# M622A.net
KiCad netlist of a schematic drawn in EAGLE
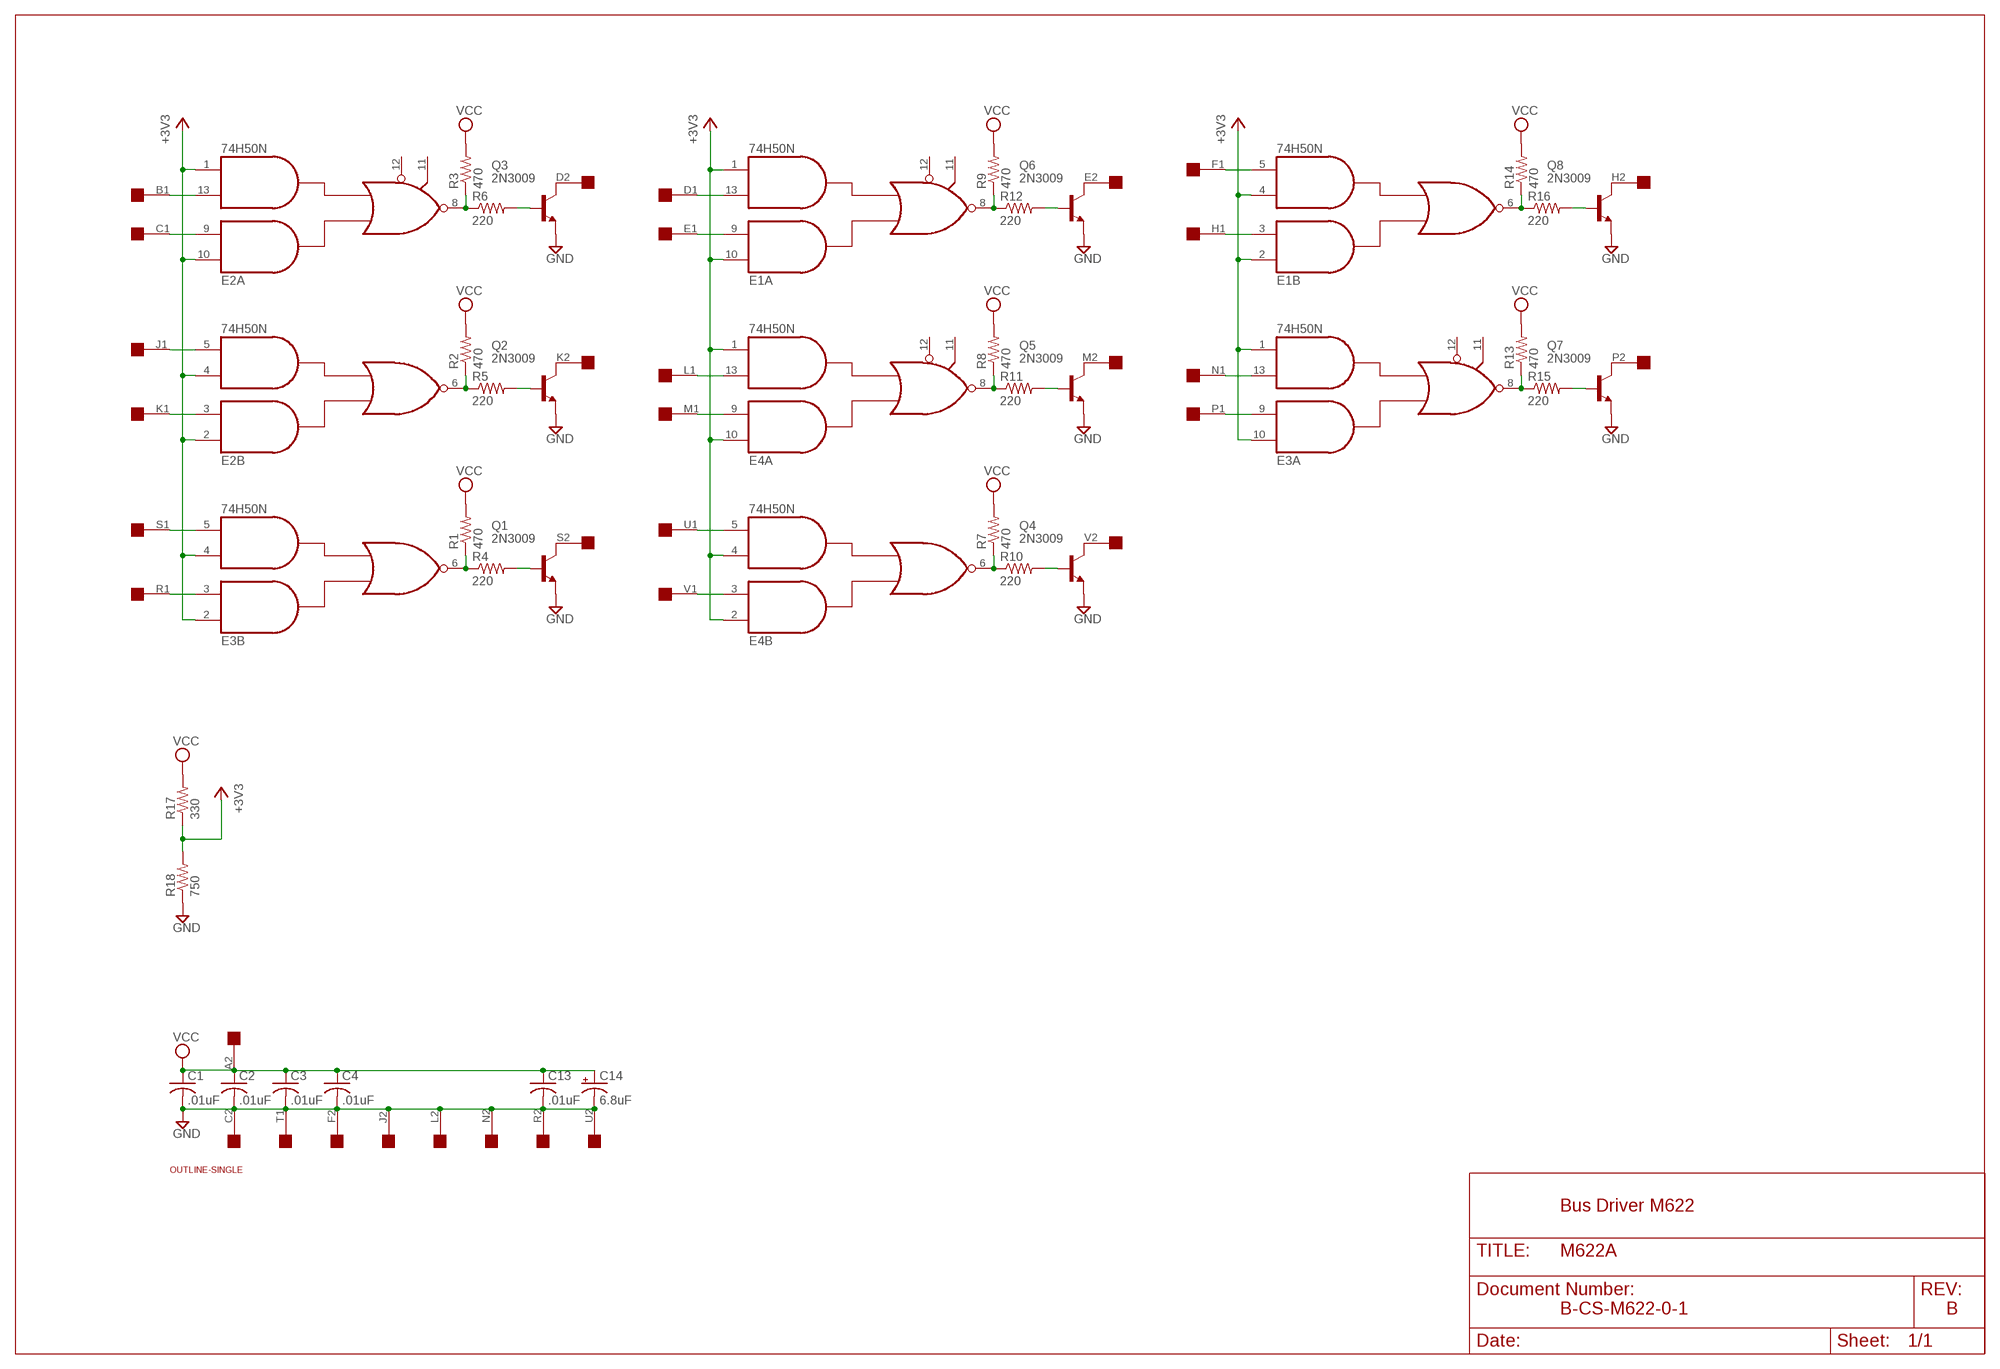
[diagram p0: schematic, sheet 1]

(export (version "E")
  (design (tool "Eeschema 10.0.6"))
  (components
    (comp (ref "C1")
      (value ".01uF")
      (footprint "eagle-import:C050-025X075")
      (libsource (lib "eagle-import") (part "C-US050-025X075"))
    )
    (comp (ref "C2")
      (value ".01uF")
      (footprint "eagle-import:C050-025X075")
      (libsource (lib "eagle-import") (part "C-US050-025X075"))
    )
    (comp (ref "C3")
      (value ".01uF")
      (footprint "eagle-import:C050-025X075")
      (libsource (lib "eagle-import") (part "C-US050-025X075"))
    )
    (comp (ref "C4")
      (value ".01uF")
      (footprint "eagle-import:C050-025X075")
      (libsource (lib "eagle-import") (part "C-US050-025X075"))
    )
    (comp (ref "C13")
      (value ".01uF")
      (footprint "eagle-import:C050-025X075")
      (libsource (lib "eagle-import") (part "C-US050-025X075"))
    )
    (comp (ref "C14")
      (value "6.8uF")
      (footprint "eagle-import:E12-8")
      (libsource (lib "eagle-import") (part "CPOL-USE20-8AXIAL"))
    )
    (comp (ref "E1")
      (value "74H50N")
      (footprint "eagle-import:DIL14")
      (libsource (lib "eagle-import") (part "7450N"))
    )
    (comp (ref "E2")
      (value "74H50N")
      (footprint "eagle-import:DIL14")
      (libsource (lib "eagle-import") (part "7450N"))
    )
    (comp (ref "E3")
      (value "74H50N")
      (footprint "eagle-import:DIL14")
      (libsource (lib "eagle-import") (part "7450N"))
    )
    (comp (ref "E4")
      (value "74H50N")
      (footprint "eagle-import:DIL14")
      (libsource (lib "eagle-import") (part "7450N"))
    )
    (comp (ref "Q1")
      (value "2N3009")
      (footprint "eagle-import:TO5")
      (libsource (lib "eagle-import") (part "2N2102"))
    )
    (comp (ref "Q2")
      (value "2N3009")
      (footprint "eagle-import:TO5")
      (libsource (lib "eagle-import") (part "2N2102"))
    )
    (comp (ref "Q3")
      (value "2N3009")
      (footprint "eagle-import:TO5")
      (libsource (lib "eagle-import") (part "2N2102"))
    )
    (comp (ref "Q4")
      (value "2N3009")
      (footprint "eagle-import:TO5")
      (libsource (lib "eagle-import") (part "2N2102"))
    )
    (comp (ref "Q5")
      (value "2N3009")
      (footprint "eagle-import:TO5")
      (libsource (lib "eagle-import") (part "2N2102"))
    )
    (comp (ref "Q6")
      (value "2N3009")
      (footprint "eagle-import:TO5")
      (libsource (lib "eagle-import") (part "2N2102"))
    )
    (comp (ref "Q7")
      (value "2N3009")
      (footprint "eagle-import:TO5")
      (libsource (lib "eagle-import") (part "2N2102"))
    )
    (comp (ref "Q8")
      (value "2N3009")
      (footprint "eagle-import:TO5")
      (libsource (lib "eagle-import") (part "2N2102"))
    )
    (comp (ref "R1")
      (value "470")
      (footprint "eagle-import:0207_10")
      (libsource (lib "eagle-import") (part "R-US_0207/10"))
    )
    (comp (ref "R2")
      (value "470")
      (footprint "eagle-import:0207_10")
      (libsource (lib "eagle-import") (part "R-US_0207/10"))
    )
    (comp (ref "R3")
      (value "470")
      (footprint "eagle-import:0207_10")
      (libsource (lib "eagle-import") (part "R-US_0207/10"))
    )
    (comp (ref "R4")
      (value "220")
      (footprint "eagle-import:0207_10")
      (libsource (lib "eagle-import") (part "R-US_0207/10"))
    )
    (comp (ref "R5")
      (value "220")
      (footprint "eagle-import:0207_10")
      (libsource (lib "eagle-import") (part "R-US_0207/10"))
    )
    (comp (ref "R6")
      (value "220")
      (footprint "eagle-import:0207_10")
      (libsource (lib "eagle-import") (part "R-US_0207/10"))
    )
    (comp (ref "R7")
      (value "470")
      (footprint "eagle-import:0207_10")
      (libsource (lib "eagle-import") (part "R-US_0207/10"))
    )
    (comp (ref "R8")
      (value "470")
      (footprint "eagle-import:0207_10")
      (libsource (lib "eagle-import") (part "R-US_0207/10"))
    )
    (comp (ref "R9")
      (value "470")
      (footprint "eagle-import:0207_10")
      (libsource (lib "eagle-import") (part "R-US_0207/10"))
    )
    (comp (ref "R10")
      (value "220")
      (footprint "eagle-import:0207_10")
      (libsource (lib "eagle-import") (part "R-US_0207/10"))
    )
    (comp (ref "R11")
      (value "220")
      (footprint "eagle-import:0207_10")
      (libsource (lib "eagle-import") (part "R-US_0207/10"))
    )
    (comp (ref "R12")
      (value "220")
      (footprint "eagle-import:0207_10")
      (libsource (lib "eagle-import") (part "R-US_0207/10"))
    )
    (comp (ref "R13")
      (value "470")
      (footprint "eagle-import:0207_10")
      (libsource (lib "eagle-import") (part "R-US_0207/10"))
    )
    (comp (ref "R14")
      (value "470")
      (footprint "eagle-import:0207_10")
      (libsource (lib "eagle-import") (part "R-US_0207/10"))
    )
    (comp (ref "R15")
      (value "220")
      (footprint "eagle-import:0207_10")
      (libsource (lib "eagle-import") (part "R-US_0207/10"))
    )
    (comp (ref "R16")
      (value "220")
      (footprint "eagle-import:0207_10")
      (libsource (lib "eagle-import") (part "R-US_0207/10"))
    )
    (comp (ref "R17")
      (value "330")
      (footprint "eagle-import:0207_10")
      (libsource (lib "eagle-import") (part "R-US_0207/10"))
    )
    (comp (ref "R18")
      (value "750")
      (footprint "eagle-import:0207_10")
      (libsource (lib "eagle-import") (part "R-US_0207/10"))
    )
    (comp (ref "U$1")
      (value "SINGLE")
      (footprint "eagle-import:EDGE-CON2")
      (libsource (lib "eagle-import") (part "SINGLE"))
    )
    (comp (ref "U$4")
      (value "OUTLINE-SINGLE")
      (footprint "eagle-import:SINGLE")
      (libsource (lib "eagle-import") (part "OUTLINE-SINGLE"))
    )
  )
  (nets
    (net (code "1") (name "+3V3") (class "Default")
      (node (ref "E1") (pin "1") (pinfunction "I4_1") (pintype "input"))
      (node (ref "E1") (pin "10") (pinfunction "I1_10") (pintype "input"))
      (node (ref "E1") (pin "2") (pinfunction "I1_2") (pintype "input"))
      (node (ref "E1") (pin "4") (pinfunction "I3_4") (pintype "input"))
      (node (ref "E2") (pin "1") (pinfunction "I4_1") (pintype "input"))
      (node (ref "E2") (pin "10") (pinfunction "I1_10") (pintype "input"))
      (node (ref "E2") (pin "2") (pinfunction "I1_2") (pintype "input"))
      (node (ref "E2") (pin "4") (pinfunction "I3_4") (pintype "input"))
      (node (ref "E3") (pin "1") (pinfunction "I4_1") (pintype "input"))
      (node (ref "E3") (pin "10") (pinfunction "I1_10") (pintype "input"))
      (node (ref "E3") (pin "2") (pinfunction "I1_2") (pintype "input"))
      (node (ref "E3") (pin "4") (pinfunction "I3_4") (pintype "input"))
      (node (ref "E4") (pin "1") (pinfunction "I4_1") (pintype "input"))
      (node (ref "E4") (pin "10") (pinfunction "I1_10") (pintype "input"))
      (node (ref "E4") (pin "2") (pinfunction "I1_2") (pintype "input"))
      (node (ref "E4") (pin "4") (pinfunction "I3_4") (pintype "input"))
      (node (ref "R17") (pin "1") (pinfunction "1_1") (pintype "passive"))
      (node (ref "R18") (pin "2") (pinfunction "2_2") (pintype "passive"))
    )
    (net (code "2") (name "GND") (class "Default")
      (node (ref "C1") (pin "2") (pinfunction "2_2") (pintype "passive"))
      (node (ref "C13") (pin "2") (pinfunction "2_2") (pintype "passive"))
      (node (ref "C14") (pin "-") (pinfunction "-_-") (pintype "passive"))
      (node (ref "C2") (pin "2") (pinfunction "2_2") (pintype "passive"))
      (node (ref "C3") (pin "2") (pinfunction "2_2") (pintype "passive"))
      (node (ref "C4") (pin "2") (pinfunction "2_2") (pintype "passive"))
      (node (ref "Q1") (pin "1") (pinfunction "E_1") (pintype "passive"))
      (node (ref "Q2") (pin "1") (pinfunction "E_1") (pintype "passive"))
      (node (ref "Q3") (pin "1") (pinfunction "E_1") (pintype "passive"))
      (node (ref "Q4") (pin "1") (pinfunction "E_1") (pintype "passive"))
      (node (ref "Q5") (pin "1") (pinfunction "E_1") (pintype "passive"))
      (node (ref "Q6") (pin "1") (pinfunction "E_1") (pintype "passive"))
      (node (ref "Q7") (pin "1") (pinfunction "E_1") (pintype "passive"))
      (node (ref "Q8") (pin "1") (pinfunction "E_1") (pintype "passive"))
      (node (ref "R18") (pin "1") (pinfunction "1_1") (pintype "passive"))
      (node (ref "U$1") (pin "C2") (pinfunction "1_C2") (pintype "bidirectional"))
      (node (ref "U$1") (pin "F2") (pinfunction "1_F2") (pintype "bidirectional"))
      (node (ref "U$1") (pin "J2") (pinfunction "1_J2") (pintype "bidirectional"))
      (node (ref "U$1") (pin "L2") (pinfunction "1_L2") (pintype "bidirectional"))
      (node (ref "U$1") (pin "N2") (pinfunction "1_N2") (pintype "bidirectional"))
      (node (ref "U$1") (pin "R2") (pinfunction "1_R2") (pintype "bidirectional"))
      (node (ref "U$1") (pin "T1") (pinfunction "1_T1") (pintype "bidirectional"))
      (node (ref "U$1") (pin "U2") (pinfunction "1_U2") (pintype "bidirectional"))
    )
    (net (code "3") (name "Net-(E1A-I2)") (class "Default")
      (node (ref "E1") (pin "9") (pinfunction "I2_9") (pintype "input"))
      (node (ref "U$1") (pin "E1") (pinfunction "1_E1") (pintype "bidirectional"))
    )
    (net (code "4") (name "Net-(E1A-I3)") (class "Default")
      (node (ref "E1") (pin "13") (pinfunction "I3_13") (pintype "input"))
      (node (ref "U$1") (pin "D1") (pinfunction "1_D1") (pintype "bidirectional"))
    )
    (net (code "5") (name "Net-(E1A-O)") (class "Default")
      (node (ref "E1") (pin "8") (pinfunction "O_8") (pintype "output"))
      (node (ref "R12") (pin "1") (pinfunction "1_1") (pintype "passive"))
      (node (ref "R9") (pin "1") (pinfunction "1_1") (pintype "passive"))
    )
    (net (code "6") (name "Net-(E1B-I2)") (class "Default")
      (node (ref "E1") (pin "3") (pinfunction "I2_3") (pintype "input"))
      (node (ref "U$1") (pin "H1") (pinfunction "1_H1") (pintype "bidirectional"))
    )
    (net (code "7") (name "Net-(E1B-I4)") (class "Default")
      (node (ref "E1") (pin "5") (pinfunction "I4_5") (pintype "input"))
      (node (ref "U$1") (pin "F1") (pinfunction "1_F1") (pintype "bidirectional"))
    )
    (net (code "8") (name "Net-(E1B-O)") (class "Default")
      (node (ref "E1") (pin "6") (pinfunction "O_6") (pintype "output"))
      (node (ref "R14") (pin "1") (pinfunction "1_1") (pintype "passive"))
      (node (ref "R16") (pin "1") (pinfunction "1_1") (pintype "passive"))
    )
    (net (code "9") (name "Net-(E2A-I2)") (class "Default")
      (node (ref "E2") (pin "9") (pinfunction "I2_9") (pintype "input"))
      (node (ref "U$1") (pin "C1") (pinfunction "1_C1") (pintype "bidirectional"))
    )
    (net (code "10") (name "Net-(E2A-I3)") (class "Default")
      (node (ref "E2") (pin "13") (pinfunction "I3_13") (pintype "input"))
      (node (ref "U$1") (pin "B1") (pinfunction "1_B1") (pintype "bidirectional"))
    )
    (net (code "11") (name "Net-(E2A-O)") (class "Default")
      (node (ref "E2") (pin "8") (pinfunction "O_8") (pintype "output"))
      (node (ref "R3") (pin "1") (pinfunction "1_1") (pintype "passive"))
      (node (ref "R6") (pin "1") (pinfunction "1_1") (pintype "passive"))
    )
    (net (code "12") (name "Net-(E2B-I2)") (class "Default")
      (node (ref "E2") (pin "3") (pinfunction "I2_3") (pintype "input"))
      (node (ref "U$1") (pin "K1") (pinfunction "1_K1") (pintype "bidirectional"))
    )
    (net (code "13") (name "Net-(E2B-I4)") (class "Default")
      (node (ref "E2") (pin "5") (pinfunction "I4_5") (pintype "input"))
      (node (ref "U$1") (pin "J1") (pinfunction "1_J1") (pintype "bidirectional"))
    )
    (net (code "14") (name "Net-(E2B-O)") (class "Default")
      (node (ref "E2") (pin "6") (pinfunction "O_6") (pintype "output"))
      (node (ref "R2") (pin "1") (pinfunction "1_1") (pintype "passive"))
      (node (ref "R5") (pin "1") (pinfunction "1_1") (pintype "passive"))
    )
    (net (code "15") (name "Net-(E3A-I2)") (class "Default")
      (node (ref "E3") (pin "9") (pinfunction "I2_9") (pintype "input"))
      (node (ref "U$1") (pin "P1") (pinfunction "1_P1") (pintype "bidirectional"))
    )
    (net (code "16") (name "Net-(E3A-I3)") (class "Default")
      (node (ref "E3") (pin "13") (pinfunction "I3_13") (pintype "input"))
      (node (ref "U$1") (pin "N1") (pinfunction "1_N1") (pintype "bidirectional"))
    )
    (net (code "17") (name "Net-(E3A-O)") (class "Default")
      (node (ref "E3") (pin "8") (pinfunction "O_8") (pintype "output"))
      (node (ref "R13") (pin "1") (pinfunction "1_1") (pintype "passive"))
      (node (ref "R15") (pin "1") (pinfunction "1_1") (pintype "passive"))
    )
    (net (code "18") (name "Net-(E3B-I2)") (class "Default")
      (node (ref "E3") (pin "3") (pinfunction "I2_3") (pintype "input"))
      (node (ref "U$1") (pin "R1") (pinfunction "1_R1") (pintype "bidirectional"))
    )
    (net (code "19") (name "Net-(E3B-I4)") (class "Default")
      (node (ref "E3") (pin "5") (pinfunction "I4_5") (pintype "input"))
      (node (ref "U$1") (pin "S1") (pinfunction "1_S1") (pintype "bidirectional"))
    )
    (net (code "20") (name "Net-(E3B-O)") (class "Default")
      (node (ref "E3") (pin "6") (pinfunction "O_6") (pintype "output"))
      (node (ref "R1") (pin "1") (pinfunction "1_1") (pintype "passive"))
      (node (ref "R4") (pin "1") (pinfunction "1_1") (pintype "passive"))
    )
    (net (code "21") (name "Net-(E4A-I2)") (class "Default")
      (node (ref "E4") (pin "9") (pinfunction "I2_9") (pintype "input"))
      (node (ref "U$1") (pin "M1") (pinfunction "1_M1") (pintype "bidirectional"))
    )
    (net (code "22") (name "Net-(E4A-I3)") (class "Default")
      (node (ref "E4") (pin "13") (pinfunction "I3_13") (pintype "input"))
      (node (ref "U$1") (pin "L1") (pinfunction "1_L1") (pintype "bidirectional"))
    )
    (net (code "23") (name "Net-(E4A-O)") (class "Default")
      (node (ref "E4") (pin "8") (pinfunction "O_8") (pintype "output"))
      (node (ref "R11") (pin "1") (pinfunction "1_1") (pintype "passive"))
      (node (ref "R8") (pin "1") (pinfunction "1_1") (pintype "passive"))
    )
    (net (code "24") (name "Net-(E4B-I2)") (class "Default")
      (node (ref "E4") (pin "3") (pinfunction "I2_3") (pintype "input"))
      (node (ref "U$1") (pin "V1") (pinfunction "1_V1") (pintype "bidirectional"))
    )
    (net (code "25") (name "Net-(E4B-I4)") (class "Default")
      (node (ref "E4") (pin "5") (pinfunction "I4_5") (pintype "input"))
      (node (ref "U$1") (pin "U1") (pinfunction "1_U1") (pintype "bidirectional"))
    )
    (net (code "26") (name "Net-(E4B-O)") (class "Default")
      (node (ref "E4") (pin "6") (pinfunction "O_6") (pintype "output"))
      (node (ref "R10") (pin "1") (pinfunction "1_1") (pintype "passive"))
      (node (ref "R7") (pin "1") (pinfunction "1_1") (pintype "passive"))
    )
    (net (code "27") (name "Net-(Q1-B)") (class "Default")
      (node (ref "Q1") (pin "2") (pinfunction "B_2") (pintype "passive"))
      (node (ref "R4") (pin "2") (pinfunction "2_2") (pintype "passive"))
    )
    (net (code "28") (name "Net-(Q1-C)") (class "Default")
      (node (ref "Q1") (pin "3") (pinfunction "C_3") (pintype "passive"))
      (node (ref "U$1") (pin "S2") (pinfunction "1_S2") (pintype "bidirectional"))
    )
    (net (code "29") (name "Net-(Q2-B)") (class "Default")
      (node (ref "Q2") (pin "2") (pinfunction "B_2") (pintype "passive"))
      (node (ref "R5") (pin "2") (pinfunction "2_2") (pintype "passive"))
    )
    (net (code "30") (name "Net-(Q2-C)") (class "Default")
      (node (ref "Q2") (pin "3") (pinfunction "C_3") (pintype "passive"))
      (node (ref "U$1") (pin "K2") (pinfunction "1_K2") (pintype "bidirectional"))
    )
    (net (code "31") (name "Net-(Q3-B)") (class "Default")
      (node (ref "Q3") (pin "2") (pinfunction "B_2") (pintype "passive"))
      (node (ref "R6") (pin "2") (pinfunction "2_2") (pintype "passive"))
    )
    (net (code "32") (name "Net-(Q3-C)") (class "Default")
      (node (ref "Q3") (pin "3") (pinfunction "C_3") (pintype "passive"))
      (node (ref "U$1") (pin "D2") (pinfunction "1_D2") (pintype "bidirectional"))
    )
    (net (code "33") (name "Net-(Q4-B)") (class "Default")
      (node (ref "Q4") (pin "2") (pinfunction "B_2") (pintype "passive"))
      (node (ref "R10") (pin "2") (pinfunction "2_2") (pintype "passive"))
    )
    (net (code "34") (name "Net-(Q4-C)") (class "Default")
      (node (ref "Q4") (pin "3") (pinfunction "C_3") (pintype "passive"))
      (node (ref "U$1") (pin "V2") (pinfunction "1_V2") (pintype "bidirectional"))
    )
    (net (code "35") (name "Net-(Q5-B)") (class "Default")
      (node (ref "Q5") (pin "2") (pinfunction "B_2") (pintype "passive"))
      (node (ref "R11") (pin "2") (pinfunction "2_2") (pintype "passive"))
    )
    (net (code "36") (name "Net-(Q5-C)") (class "Default")
      (node (ref "Q5") (pin "3") (pinfunction "C_3") (pintype "passive"))
      (node (ref "U$1") (pin "M2") (pinfunction "1_M2") (pintype "bidirectional"))
    )
    (net (code "37") (name "Net-(Q6-B)") (class "Default")
      (node (ref "Q6") (pin "2") (pinfunction "B_2") (pintype "passive"))
      (node (ref "R12") (pin "2") (pinfunction "2_2") (pintype "passive"))
    )
    (net (code "38") (name "Net-(Q6-C)") (class "Default")
      (node (ref "Q6") (pin "3") (pinfunction "C_3") (pintype "passive"))
      (node (ref "U$1") (pin "E2") (pinfunction "1_E2") (pintype "bidirectional"))
    )
    (net (code "39") (name "Net-(Q7-B)") (class "Default")
      (node (ref "Q7") (pin "2") (pinfunction "B_2") (pintype "passive"))
      (node (ref "R15") (pin "2") (pinfunction "2_2") (pintype "passive"))
    )
    (net (code "40") (name "Net-(Q7-C)") (class "Default")
      (node (ref "Q7") (pin "3") (pinfunction "C_3") (pintype "passive"))
      (node (ref "U$1") (pin "P2") (pinfunction "1_P2") (pintype "bidirectional"))
    )
    (net (code "41") (name "Net-(Q8-B)") (class "Default")
      (node (ref "Q8") (pin "2") (pinfunction "B_2") (pintype "passive"))
      (node (ref "R16") (pin "2") (pinfunction "2_2") (pintype "passive"))
    )
    (net (code "42") (name "Net-(Q8-C)") (class "Default")
      (node (ref "Q8") (pin "3") (pinfunction "C_3") (pintype "passive"))
      (node (ref "U$1") (pin "H2") (pinfunction "1_H2") (pintype "bidirectional"))
    )
    (net (code "43") (name "VCC") (class "Default")
      (node (ref "C1") (pin "1") (pinfunction "1_1") (pintype "passive"))
      (node (ref "C13") (pin "1") (pinfunction "1_1") (pintype "passive"))
      (node (ref "C14") (pin "+") (pinfunction "+_+") (pintype "passive"))
      (node (ref "C2") (pin "1") (pinfunction "1_1") (pintype "passive"))
      (node (ref "C3") (pin "1") (pinfunction "1_1") (pintype "passive"))
      (node (ref "C4") (pin "1") (pinfunction "1_1") (pintype "passive"))
      (node (ref "R1") (pin "2") (pinfunction "2_2") (pintype "passive"))
      (node (ref "R13") (pin "2") (pinfunction "2_2") (pintype "passive"))
      (node (ref "R14") (pin "2") (pinfunction "2_2") (pintype "passive"))
      (node (ref "R17") (pin "2") (pinfunction "2_2") (pintype "passive"))
      (node (ref "R2") (pin "2") (pinfunction "2_2") (pintype "passive"))
      (node (ref "R3") (pin "2") (pinfunction "2_2") (pintype "passive"))
      (node (ref "R7") (pin "2") (pinfunction "2_2") (pintype "passive"))
      (node (ref "R8") (pin "2") (pinfunction "2_2") (pintype "passive"))
      (node (ref "R9") (pin "2") (pinfunction "2_2") (pintype "passive"))
      (node (ref "U$1") (pin "A2") (pinfunction "1_A2") (pintype "bidirectional"))
    )
    (net (code "44") (name "unconnected-(E1A-I5-Pad12)") (class "Default")
      (node (ref "E1") (pin "12") (pinfunction "I5_12") (pintype "passive"))
    )
    (net (code "45") (name "unconnected-(E1A-I6-Pad11)") (class "Default")
      (node (ref "E1") (pin "11") (pinfunction "I6_11") (pintype "passive"))
    )
    (net (code "46") (name "unconnected-(E2A-I5-Pad12)") (class "Default")
      (node (ref "E2") (pin "12") (pinfunction "I5_12") (pintype "passive"))
    )
    (net (code "47") (name "unconnected-(E2A-I6-Pad11)") (class "Default")
      (node (ref "E2") (pin "11") (pinfunction "I6_11") (pintype "passive"))
    )
    (net (code "48") (name "unconnected-(E3A-I5-Pad12)") (class "Default")
      (node (ref "E3") (pin "12") (pinfunction "I5_12") (pintype "passive"))
    )
    (net (code "49") (name "unconnected-(E3A-I6-Pad11)") (class "Default")
      (node (ref "E3") (pin "11") (pinfunction "I6_11") (pintype "passive"))
    )
    (net (code "50") (name "unconnected-(E4A-I5-Pad12)") (class "Default")
      (node (ref "E4") (pin "12") (pinfunction "I5_12") (pintype "passive"))
    )
    (net (code "51") (name "unconnected-(E4A-I6-Pad11)") (class "Default")
      (node (ref "E4") (pin "11") (pinfunction "I6_11") (pintype "passive"))
    )
  )
)
